# BANK14-15.net
KiCad netlist of a schematic drawn in Altium Designer
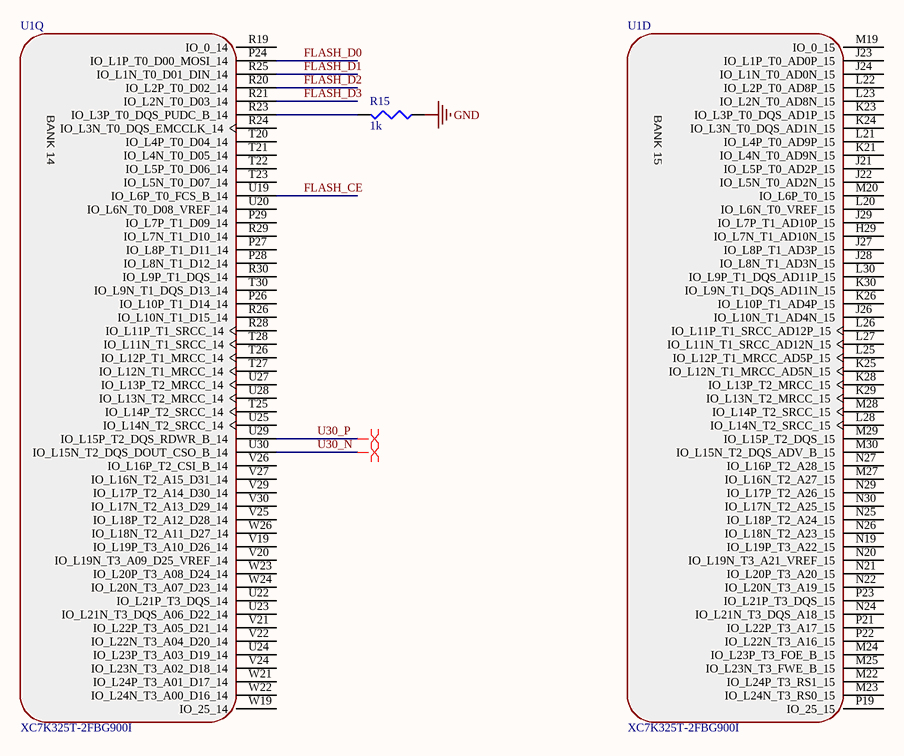
[diagram p0: BANK14-15.SchDoc]

(export (version "E")
  (design (tool "Eeschema 10.0.6"))
  (components
    (comp (ref "R15")
      (value "1k")
      (footprint "J1-0603")
      (description "Resistor")
      (fields (field (name "Comment") "Res3") (field (name "PUBLISHER") "Altium Limited"))
      (libsource (lib "Miscellaneous Devices") (part "Res3"))
    )
    (comp (ref "U1")
      (value "XC7K325T-2FBG900I")
      (footprint "FBG900")
      (libsource (lib "Schlib1") (part "XC7K325T-2FBG900I"))
    )
  )
  (nets
    (net (code "1") (name "/FLASH_CE") (class "Default")
      (node (ref "U1") (pin "U19") (pinfunction "IO_L6P_T0_FCS_B_14_U19") (pintype "passive"))
    )
    (net (code "2") (name "/FLASH_D0") (class "Default")
      (node (ref "U1") (pin "P24") (pinfunction "IO_L1P_T0_D00_MOSI_14_P24") (pintype "passive"))
    )
    (net (code "3") (name "/FLASH_D1") (class "Default")
      (node (ref "U1") (pin "R25") (pinfunction "IO_L1N_T0_D01_DIN_14_R25") (pintype "passive"))
    )
    (net (code "4") (name "/FLASH_D2") (class "Default")
      (node (ref "U1") (pin "R20") (pinfunction "IO_L2P_T0_D02_14_R20") (pintype "passive"))
    )
    (net (code "5") (name "/FLASH_D3") (class "Default")
      (node (ref "U1") (pin "R21") (pinfunction "IO_L2N_T0_D03_14_R21") (pintype "passive"))
    )
    (net (code "6") (name "/U30_N") (class "Default")
      (node (ref "U1") (pin "U30") (pinfunction "IO_L15N_T2_DQS_DOUT_CSO_B_14_U30") (pintype "passive"))
    )
    (net (code "7") (name "/U30_P") (class "Default")
      (node (ref "U1") (pin "U29") (pinfunction "IO_L15P_T2_DQS_RDWR_B_14_U29") (pintype "passive"))
    )
    (net (code "8") (name "GND") (class "Default")
      (node (ref "R15") (pin "1") (pinfunction "1_1") (pintype "passive"))
    )
    (net (code "9") (name "Net-(U1Q-IO_L3P_T0_DQS_PUDC_B_14)") (class "Default")
      (node (ref "R15") (pin "2") (pinfunction "2_2") (pintype "passive"))
      (node (ref "U1") (pin "R23") (pinfunction "IO_L3P_T0_DQS_PUDC_B_14_R23") (pintype "passive"))
    )
    (net (code "10") (name "unconnected-(U1D-IO_0_15-PadM19)") (class "Default")
      (node (ref "U1") (pin "M19") (pinfunction "IO_0_15_M19") (pintype "passive"))
    )
    (net (code "11") (name "unconnected-(U1D-IO_25_15-PadP19)") (class "Default")
      (node (ref "U1") (pin "P19") (pinfunction "IO_25_15_P19") (pintype "passive"))
    )
    (net (code "12") (name "unconnected-(U1D-IO_L1N_T0_AD0N_15-PadJ24)") (class "Default")
      (node (ref "U1") (pin "J24") (pinfunction "IO_L1N_T0_AD0N_15_J24") (pintype "passive"))
    )
    (net (code "13") (name "unconnected-(U1D-IO_L1P_T0_AD0P_15-PadJ23)") (class "Default")
      (node (ref "U1") (pin "J23") (pinfunction "IO_L1P_T0_AD0P_15_J23") (pintype "passive"))
    )
    (net (code "14") (name "unconnected-(U1D-IO_L2N_T0_AD8N_15-PadL23)") (class "Default")
      (node (ref "U1") (pin "L23") (pinfunction "IO_L2N_T0_AD8N_15_L23") (pintype "passive"))
    )
    (net (code "15") (name "unconnected-(U1D-IO_L2P_T0_AD8P_15-PadL22)") (class "Default")
      (node (ref "U1") (pin "L22") (pinfunction "IO_L2P_T0_AD8P_15_L22") (pintype "passive"))
    )
    (net (code "16") (name "unconnected-(U1D-IO_L3N_T0_DQS_AD1N_15-PadK24)") (class "Default")
      (node (ref "U1") (pin "K24") (pinfunction "IO_L3N_T0_DQS_AD1N_15_K24") (pintype "passive"))
    )
    (net (code "17") (name "unconnected-(U1D-IO_L3P_T0_DQS_AD1P_15-PadK23)") (class "Default")
      (node (ref "U1") (pin "K23") (pinfunction "IO_L3P_T0_DQS_AD1P_15_K23") (pintype "passive"))
    )
    (net (code "18") (name "unconnected-(U1D-IO_L4N_T0_AD9N_15-PadK21)") (class "Default")
      (node (ref "U1") (pin "K21") (pinfunction "IO_L4N_T0_AD9N_15_K21") (pintype "passive"))
    )
    (net (code "19") (name "unconnected-(U1D-IO_L4P_T0_AD9P_15-PadL21)") (class "Default")
      (node (ref "U1") (pin "L21") (pinfunction "IO_L4P_T0_AD9P_15_L21") (pintype "passive"))
    )
    (net (code "20") (name "unconnected-(U1D-IO_L5N_T0_AD2N_15-PadJ22)") (class "Default")
      (node (ref "U1") (pin "J22") (pinfunction "IO_L5N_T0_AD2N_15_J22") (pintype "passive"))
    )
    (net (code "21") (name "unconnected-(U1D-IO_L5P_T0_AD2P_15-PadJ21)") (class "Default")
      (node (ref "U1") (pin "J21") (pinfunction "IO_L5P_T0_AD2P_15_J21") (pintype "passive"))
    )
    (net (code "22") (name "unconnected-(U1D-IO_L6N_T0_VREF_15-PadL20)") (class "Default")
      (node (ref "U1") (pin "L20") (pinfunction "IO_L6N_T0_VREF_15_L20") (pintype "passive"))
    )
    (net (code "23") (name "unconnected-(U1D-IO_L6P_T0_15-PadM20)") (class "Default")
      (node (ref "U1") (pin "M20") (pinfunction "IO_L6P_T0_15_M20") (pintype "passive"))
    )
    (net (code "24") (name "unconnected-(U1D-IO_L7N_T1_AD10N_15-PadH29)") (class "Default")
      (node (ref "U1") (pin "H29") (pinfunction "IO_L7N_T1_AD10N_15_H29") (pintype "passive"))
    )
    (net (code "25") (name "unconnected-(U1D-IO_L7P_T1_AD10P_15-PadJ29)") (class "Default")
      (node (ref "U1") (pin "J29") (pinfunction "IO_L7P_T1_AD10P_15_J29") (pintype "passive"))
    )
    (net (code "26") (name "unconnected-(U1D-IO_L8N_T1_AD3N_15-PadJ28)") (class "Default")
      (node (ref "U1") (pin "J28") (pinfunction "IO_L8N_T1_AD3N_15_J28") (pintype "passive"))
    )
    (net (code "27") (name "unconnected-(U1D-IO_L8P_T1_AD3P_15-PadJ27)") (class "Default")
      (node (ref "U1") (pin "J27") (pinfunction "IO_L8P_T1_AD3P_15_J27") (pintype "passive"))
    )
    (net (code "28") (name "unconnected-(U1D-IO_L9N_T1_DQS_AD11N_15-PadK30)") (class "Default")
      (node (ref "U1") (pin "K30") (pinfunction "IO_L9N_T1_DQS_AD11N_15_K30") (pintype "passive"))
    )
    (net (code "29") (name "unconnected-(U1D-IO_L9P_T1_DQS_AD11P_15-PadL30)") (class "Default")
      (node (ref "U1") (pin "L30") (pinfunction "IO_L9P_T1_DQS_AD11P_15_L30") (pintype "passive"))
    )
    (net (code "30") (name "unconnected-(U1D-IO_L10N_T1_AD4N_15-PadJ26)") (class "Default")
      (node (ref "U1") (pin "J26") (pinfunction "IO_L10N_T1_AD4N_15_J26") (pintype "passive"))
    )
    (net (code "31") (name "unconnected-(U1D-IO_L10P_T1_AD4P_15-PadK26)") (class "Default")
      (node (ref "U1") (pin "K26") (pinfunction "IO_L10P_T1_AD4P_15_K26") (pintype "passive"))
    )
    (net (code "32") (name "unconnected-(U1D-IO_L11N_T1_SRCC_AD12N_15-PadL27)") (class "Default")
      (node (ref "U1") (pin "L27") (pinfunction "IO_L11N_T1_SRCC_AD12N_15_L27") (pintype "passive"))
    )
    (net (code "33") (name "unconnected-(U1D-IO_L11P_T1_SRCC_AD12P_15-PadL26)") (class "Default")
      (node (ref "U1") (pin "L26") (pinfunction "IO_L11P_T1_SRCC_AD12P_15_L26") (pintype "passive"))
    )
    (net (code "34") (name "unconnected-(U1D-IO_L12N_T1_MRCC_AD5N_15-PadK25)") (class "Default")
      (node (ref "U1") (pin "K25") (pinfunction "IO_L12N_T1_MRCC_AD5N_15_K25") (pintype "passive"))
    )
    (net (code "35") (name "unconnected-(U1D-IO_L12P_T1_MRCC_AD5P_15-PadL25)") (class "Default")
      (node (ref "U1") (pin "L25") (pinfunction "IO_L12P_T1_MRCC_AD5P_15_L25") (pintype "passive"))
    )
    (net (code "36") (name "unconnected-(U1D-IO_L13N_T2_MRCC_15-PadK29)") (class "Default")
      (node (ref "U1") (pin "K29") (pinfunction "IO_L13N_T2_MRCC_15_K29") (pintype "passive"))
    )
    (net (code "37") (name "unconnected-(U1D-IO_L13P_T2_MRCC_15-PadK28)") (class "Default")
      (node (ref "U1") (pin "K28") (pinfunction "IO_L13P_T2_MRCC_15_K28") (pintype "passive"))
    )
    (net (code "38") (name "unconnected-(U1D-IO_L14N_T2_SRCC_15-PadL28)") (class "Default")
      (node (ref "U1") (pin "L28") (pinfunction "IO_L14N_T2_SRCC_15_L28") (pintype "passive"))
    )
    (net (code "39") (name "unconnected-(U1D-IO_L14P_T2_SRCC_15-PadM28)") (class "Default")
      (node (ref "U1") (pin "M28") (pinfunction "IO_L14P_T2_SRCC_15_M28") (pintype "passive"))
    )
    (net (code "40") (name "unconnected-(U1D-IO_L15N_T2_DQS_ADV_B_15-PadM30)") (class "Default")
      (node (ref "U1") (pin "M30") (pinfunction "IO_L15N_T2_DQS_ADV_B_15_M30") (pintype "passive"))
    )
    (net (code "41") (name "unconnected-(U1D-IO_L15P_T2_DQS_15-PadM29)") (class "Default")
      (node (ref "U1") (pin "M29") (pinfunction "IO_L15P_T2_DQS_15_M29") (pintype "passive"))
    )
    (net (code "42") (name "unconnected-(U1D-IO_L16N_T2_A27_15-PadM27)") (class "Default")
      (node (ref "U1") (pin "M27") (pinfunction "IO_L16N_T2_A27_15_M27") (pintype "passive"))
    )
    (net (code "43") (name "unconnected-(U1D-IO_L16P_T2_A28_15-PadN27)") (class "Default")
      (node (ref "U1") (pin "N27") (pinfunction "IO_L16P_T2_A28_15_N27") (pintype "passive"))
    )
    (net (code "44") (name "unconnected-(U1D-IO_L17N_T2_A25_15-PadN30)") (class "Default")
      (node (ref "U1") (pin "N30") (pinfunction "IO_L17N_T2_A25_15_N30") (pintype "passive"))
    )
    (net (code "45") (name "unconnected-(U1D-IO_L17P_T2_A26_15-PadN29)") (class "Default")
      (node (ref "U1") (pin "N29") (pinfunction "IO_L17P_T2_A26_15_N29") (pintype "passive"))
    )
    (net (code "46") (name "unconnected-(U1D-IO_L18N_T2_A23_15-PadN26)") (class "Default")
      (node (ref "U1") (pin "N26") (pinfunction "IO_L18N_T2_A23_15_N26") (pintype "passive"))
    )
    (net (code "47") (name "unconnected-(U1D-IO_L18P_T2_A24_15-PadN25)") (class "Default")
      (node (ref "U1") (pin "N25") (pinfunction "IO_L18P_T2_A24_15_N25") (pintype "passive"))
    )
    (net (code "48") (name "unconnected-(U1D-IO_L19N_T3_A21_VREF_15-PadN20)") (class "Default")
      (node (ref "U1") (pin "N20") (pinfunction "IO_L19N_T3_A21_VREF_15_N20") (pintype "passive"))
    )
    (net (code "49") (name "unconnected-(U1D-IO_L19P_T3_A22_15-PadN19)") (class "Default")
      (node (ref "U1") (pin "N19") (pinfunction "IO_L19P_T3_A22_15_N19") (pintype "passive"))
    )
    (net (code "50") (name "unconnected-(U1D-IO_L20N_T3_A19_15-PadN22)") (class "Default")
      (node (ref "U1") (pin "N22") (pinfunction "IO_L20N_T3_A19_15_N22") (pintype "passive"))
    )
    (net (code "51") (name "unconnected-(U1D-IO_L20P_T3_A20_15-PadN21)") (class "Default")
      (node (ref "U1") (pin "N21") (pinfunction "IO_L20P_T3_A20_15_N21") (pintype "passive"))
    )
    (net (code "52") (name "unconnected-(U1D-IO_L21N_T3_DQS_A18_15-PadN24)") (class "Default")
      (node (ref "U1") (pin "N24") (pinfunction "IO_L21N_T3_DQS_A18_15_N24") (pintype "passive"))
    )
    (net (code "53") (name "unconnected-(U1D-IO_L21P_T3_DQS_15-PadP23)") (class "Default")
      (node (ref "U1") (pin "P23") (pinfunction "IO_L21P_T3_DQS_15_P23") (pintype "passive"))
    )
    (net (code "54") (name "unconnected-(U1D-IO_L22N_T3_A16_15-PadP22)") (class "Default")
      (node (ref "U1") (pin "P22") (pinfunction "IO_L22N_T3_A16_15_P22") (pintype "passive"))
    )
    (net (code "55") (name "unconnected-(U1D-IO_L22P_T3_A17_15-PadP21)") (class "Default")
      (node (ref "U1") (pin "P21") (pinfunction "IO_L22P_T3_A17_15_P21") (pintype "passive"))
    )
    (net (code "56") (name "unconnected-(U1D-IO_L23N_T3_FWE_B_15-PadM25)") (class "Default")
      (node (ref "U1") (pin "M25") (pinfunction "IO_L23N_T3_FWE_B_15_M25") (pintype "passive"))
    )
    (net (code "57") (name "unconnected-(U1D-IO_L23P_T3_FOE_B_15-PadM24)") (class "Default")
      (node (ref "U1") (pin "M24") (pinfunction "IO_L23P_T3_FOE_B_15_M24") (pintype "passive"))
    )
    (net (code "58") (name "unconnected-(U1D-IO_L24N_T3_RS0_15-PadM23)") (class "Default")
      (node (ref "U1") (pin "M23") (pinfunction "IO_L24N_T3_RS0_15_M23") (pintype "passive"))
    )
    (net (code "59") (name "unconnected-(U1D-IO_L24P_T3_RS1_15-PadM22)") (class "Default")
      (node (ref "U1") (pin "M22") (pinfunction "IO_L24P_T3_RS1_15_M22") (pintype "passive"))
    )
    (net (code "60") (name "unconnected-(U1Q-IO_0_14-PadR19)") (class "Default")
      (node (ref "U1") (pin "R19") (pinfunction "IO_0_14_R19") (pintype "passive"))
    )
    (net (code "61") (name "unconnected-(U1Q-IO_25_14-PadW19)") (class "Default")
      (node (ref "U1") (pin "W19") (pinfunction "IO_25_14_W19") (pintype "passive"))
    )
    (net (code "62") (name "unconnected-(U1Q-IO_L3N_T0_DQS_EMCCLK_14-PadR24)") (class "Default")
      (node (ref "U1") (pin "R24") (pinfunction "IO_L3N_T0_DQS_EMCCLK_14_R24") (pintype "passive"))
    )
    (net (code "63") (name "unconnected-(U1Q-IO_L4N_T0_D05_14-PadT21)") (class "Default")
      (node (ref "U1") (pin "T21") (pinfunction "IO_L4N_T0_D05_14_T21") (pintype "passive"))
    )
    (net (code "64") (name "unconnected-(U1Q-IO_L4P_T0_D04_14-PadT20)") (class "Default")
      (node (ref "U1") (pin "T20") (pinfunction "IO_L4P_T0_D04_14_T20") (pintype "passive"))
    )
    (net (code "65") (name "unconnected-(U1Q-IO_L5N_T0_D07_14-PadT23)") (class "Default")
      (node (ref "U1") (pin "T23") (pinfunction "IO_L5N_T0_D07_14_T23") (pintype "passive"))
    )
    (net (code "66") (name "unconnected-(U1Q-IO_L5P_T0_D06_14-PadT22)") (class "Default")
      (node (ref "U1") (pin "T22") (pinfunction "IO_L5P_T0_D06_14_T22") (pintype "passive"))
    )
    (net (code "67") (name "unconnected-(U1Q-IO_L6N_T0_D08_VREF_14-PadU20)") (class "Default")
      (node (ref "U1") (pin "U20") (pinfunction "IO_L6N_T0_D08_VREF_14_U20") (pintype "passive"))
    )
    (net (code "68") (name "unconnected-(U1Q-IO_L7N_T1_D10_14-PadR29)") (class "Default")
      (node (ref "U1") (pin "R29") (pinfunction "IO_L7N_T1_D10_14_R29") (pintype "passive"))
    )
    (net (code "69") (name "unconnected-(U1Q-IO_L7P_T1_D09_14-PadP29)") (class "Default")
      (node (ref "U1") (pin "P29") (pinfunction "IO_L7P_T1_D09_14_P29") (pintype "passive"))
    )
    (net (code "70") (name "unconnected-(U1Q-IO_L8N_T1_D12_14-PadP28)") (class "Default")
      (node (ref "U1") (pin "P28") (pinfunction "IO_L8N_T1_D12_14_P28") (pintype "passive"))
    )
    (net (code "71") (name "unconnected-(U1Q-IO_L8P_T1_D11_14-PadP27)") (class "Default")
      (node (ref "U1") (pin "P27") (pinfunction "IO_L8P_T1_D11_14_P27") (pintype "passive"))
    )
    (net (code "72") (name "unconnected-(U1Q-IO_L9N_T1_DQS_D13_14-PadT30)") (class "Default")
      (node (ref "U1") (pin "T30") (pinfunction "IO_L9N_T1_DQS_D13_14_T30") (pintype "passive"))
    )
    (net (code "73") (name "unconnected-(U1Q-IO_L9P_T1_DQS_14-PadR30)") (class "Default")
      (node (ref "U1") (pin "R30") (pinfunction "IO_L9P_T1_DQS_14_R30") (pintype "passive"))
    )
    (net (code "74") (name "unconnected-(U1Q-IO_L10N_T1_D15_14-PadR26)") (class "Default")
      (node (ref "U1") (pin "R26") (pinfunction "IO_L10N_T1_D15_14_R26") (pintype "passive"))
    )
    (net (code "75") (name "unconnected-(U1Q-IO_L10P_T1_D14_14-PadP26)") (class "Default")
      (node (ref "U1") (pin "P26") (pinfunction "IO_L10P_T1_D14_14_P26") (pintype "passive"))
    )
    (net (code "76") (name "unconnected-(U1Q-IO_L11N_T1_SRCC_14-PadT28)") (class "Default")
      (node (ref "U1") (pin "T28") (pinfunction "IO_L11N_T1_SRCC_14_T28") (pintype "passive"))
    )
    (net (code "77") (name "unconnected-(U1Q-IO_L11P_T1_SRCC_14-PadR28)") (class "Default")
      (node (ref "U1") (pin "R28") (pinfunction "IO_L11P_T1_SRCC_14_R28") (pintype "passive"))
    )
    (net (code "78") (name "unconnected-(U1Q-IO_L12N_T1_MRCC_14-PadT27)") (class "Default")
      (node (ref "U1") (pin "T27") (pinfunction "IO_L12N_T1_MRCC_14_T27") (pintype "passive"))
    )
    (net (code "79") (name "unconnected-(U1Q-IO_L12P_T1_MRCC_14-PadT26)") (class "Default")
      (node (ref "U1") (pin "T26") (pinfunction "IO_L12P_T1_MRCC_14_T26") (pintype "passive"))
    )
    (net (code "80") (name "unconnected-(U1Q-IO_L13N_T2_MRCC_14-PadU28)") (class "Default")
      (node (ref "U1") (pin "U28") (pinfunction "IO_L13N_T2_MRCC_14_U28") (pintype "passive"))
    )
    (net (code "81") (name "unconnected-(U1Q-IO_L13P_T2_MRCC_14-PadU27)") (class "Default")
      (node (ref "U1") (pin "U27") (pinfunction "IO_L13P_T2_MRCC_14_U27") (pintype "passive"))
    )
    (net (code "82") (name "unconnected-(U1Q-IO_L14N_T2_SRCC_14-PadU25)") (class "Default")
      (node (ref "U1") (pin "U25") (pinfunction "IO_L14N_T2_SRCC_14_U25") (pintype "passive"))
    )
    (net (code "83") (name "unconnected-(U1Q-IO_L14P_T2_SRCC_14-PadT25)") (class "Default")
      (node (ref "U1") (pin "T25") (pinfunction "IO_L14P_T2_SRCC_14_T25") (pintype "passive"))
    )
    (net (code "84") (name "unconnected-(U1Q-IO_L16N_T2_A15_D31_14-PadV27)") (class "Default")
      (node (ref "U1") (pin "V27") (pinfunction "IO_L16N_T2_A15_D31_14_V27") (pintype "passive"))
    )
    (net (code "85") (name "unconnected-(U1Q-IO_L16P_T2_CSI_B_14-PadV26)") (class "Default")
      (node (ref "U1") (pin "V26") (pinfunction "IO_L16P_T2_CSI_B_14_V26") (pintype "passive"))
    )
    (net (code "86") (name "unconnected-(U1Q-IO_L17N_T2_A13_D29_14-PadV30)") (class "Default")
      (node (ref "U1") (pin "V30") (pinfunction "IO_L17N_T2_A13_D29_14_V30") (pintype "passive"))
    )
    (net (code "87") (name "unconnected-(U1Q-IO_L17P_T2_A14_D30_14-PadV29)") (class "Default")
      (node (ref "U1") (pin "V29") (pinfunction "IO_L17P_T2_A14_D30_14_V29") (pintype "passive"))
    )
    (net (code "88") (name "unconnected-(U1Q-IO_L18N_T2_A11_D27_14-PadW26)") (class "Default")
      (node (ref "U1") (pin "W26") (pinfunction "IO_L18N_T2_A11_D27_14_W26") (pintype "passive"))
    )
    (net (code "89") (name "unconnected-(U1Q-IO_L18P_T2_A12_D28_14-PadV25)") (class "Default")
      (node (ref "U1") (pin "V25") (pinfunction "IO_L18P_T2_A12_D28_14_V25") (pintype "passive"))
    )
    (net (code "90") (name "unconnected-(U1Q-IO_L19N_T3_A09_D25_VREF_14-PadV20)") (class "Default")
      (node (ref "U1") (pin "V20") (pinfunction "IO_L19N_T3_A09_D25_VREF_14_V20") (pintype "passive"))
    )
    (net (code "91") (name "unconnected-(U1Q-IO_L19P_T3_A10_D26_14-PadV19)") (class "Default")
      (node (ref "U1") (pin "V19") (pinfunction "IO_L19P_T3_A10_D26_14_V19") (pintype "passive"))
    )
    (net (code "92") (name "unconnected-(U1Q-IO_L20N_T3_A07_D23_14-PadW24)") (class "Default")
      (node (ref "U1") (pin "W24") (pinfunction "IO_L20N_T3_A07_D23_14_W24") (pintype "passive"))
    )
    (net (code "93") (name "unconnected-(U1Q-IO_L20P_T3_A08_D24_14-PadW23)") (class "Default")
      (node (ref "U1") (pin "W23") (pinfunction "IO_L20P_T3_A08_D24_14_W23") (pintype "passive"))
    )
    (net (code "94") (name "unconnected-(U1Q-IO_L21N_T3_DQS_A06_D22_14-PadU23)") (class "Default")
      (node (ref "U1") (pin "U23") (pinfunction "IO_L21N_T3_DQS_A06_D22_14_U23") (pintype "passive"))
    )
    (net (code "95") (name "unconnected-(U1Q-IO_L21P_T3_DQS_14-PadU22)") (class "Default")
      (node (ref "U1") (pin "U22") (pinfunction "IO_L21P_T3_DQS_14_U22") (pintype "passive"))
    )
    (net (code "96") (name "unconnected-(U1Q-IO_L22N_T3_A04_D20_14-PadV22)") (class "Default")
      (node (ref "U1") (pin "V22") (pinfunction "IO_L22N_T3_A04_D20_14_V22") (pintype "passive"))
    )
    (net (code "97") (name "unconnected-(U1Q-IO_L22P_T3_A05_D21_14-PadV21)") (class "Default")
      (node (ref "U1") (pin "V21") (pinfunction "IO_L22P_T3_A05_D21_14_V21") (pintype "passive"))
    )
    (net (code "98") (name "unconnected-(U1Q-IO_L23N_T3_A02_D18_14-PadV24)") (class "Default")
      (node (ref "U1") (pin "V24") (pinfunction "IO_L23N_T3_A02_D18_14_V24") (pintype "passive"))
    )
    (net (code "99") (name "unconnected-(U1Q-IO_L23P_T3_A03_D19_14-PadU24)") (class "Default")
      (node (ref "U1") (pin "U24") (pinfunction "IO_L23P_T3_A03_D19_14_U24") (pintype "passive"))
    )
    (net (code "100") (name "unconnected-(U1Q-IO_L24N_T3_A00_D16_14-PadW22)") (class "Default")
      (node (ref "U1") (pin "W22") (pinfunction "IO_L24N_T3_A00_D16_14_W22") (pintype "passive"))
    )
    (net (code "101") (name "unconnected-(U1Q-IO_L24P_T3_A01_D17_14-PadW21)") (class "Default")
      (node (ref "U1") (pin "W21") (pinfunction "IO_L24P_T3_A01_D17_14_W21") (pintype "passive"))
    )
  )
)
